# STB_DUTcarrier.net
KiCad netlist of a schematic drawn in Altium Designer
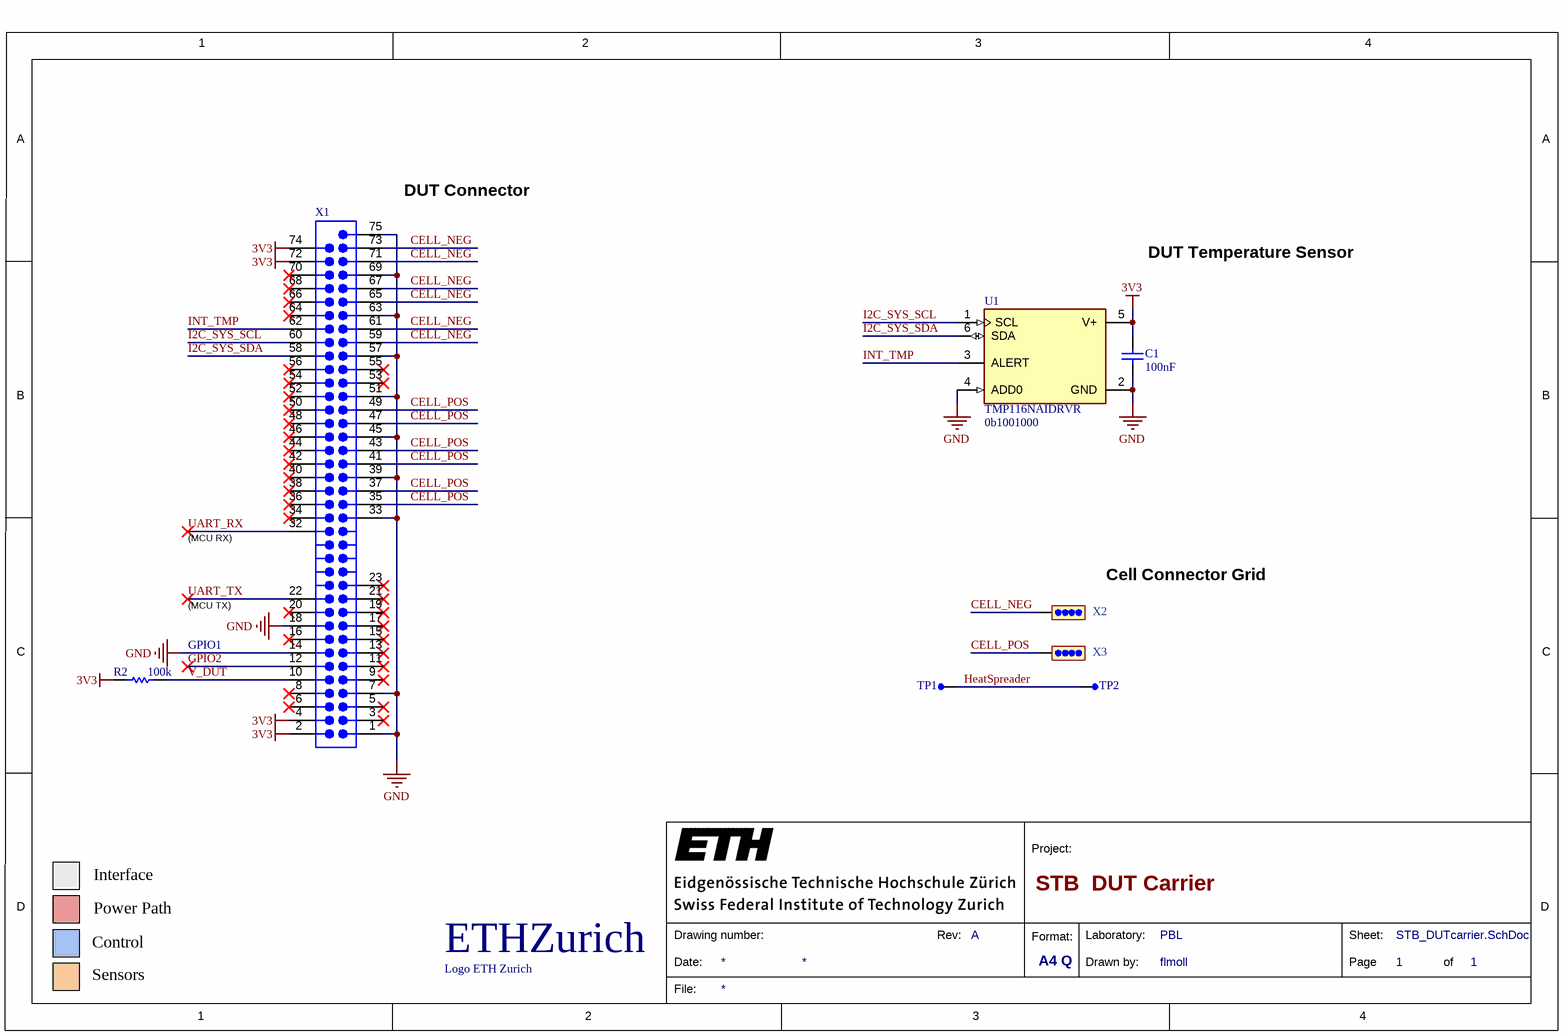
[diagram p0: STB_DUTcarrier.SchDoc]

(export (version "E")
  (design (tool "Eeschema 10.0.6"))
  (components
    (comp (ref "A1")
      (value "Logo ETH Zurich")
      (footprint "eth-zurich_5mm")
      (libsource (lib "ETHZ Vault") (part "Logo ETH Zurich"))
    )
    (comp (ref "C1")
      (value "100nF")
      (footprint "CAPC1050X55X23LL05T13")
      (description "Chip Capacitor, 100 nF, +/- 10%, 16 V, -55 to 125 degC, 0402 (1005 Metric), RoHS, Tape and Reel")
      (fields
        (field (name "MANUFACTURER") "Samsung Electro-Mechanics")
        (field (name "MANUFACTURER PART NUMBER") "CL05B104KO5NNNC")
      )
      (libsource (lib "Altium Content Vault") (part "CAP-NP-2"))
    )
    (comp (ref "R2")
      (value "100k")
      (footprint "RESC1005X40X25LL05T10")
      (fields
        (field (name "PART NUMBER") "RC0402FR-07100KL")
        (field (name "MANUFACTURER") "Yageo / Phycomp")
        (field (name "TOLERANCE") "1%")
      )
      (libsource (lib "Altium Content Vault") (part "RES"))
    )
    (comp (ref "TP1")
      (value "testPoint_1mm")
      (footprint "TP-SM-C-100")
      (description "testPoint 1mm")
      (libsource (lib "STB_Schlib") (part "testPoint_1mm"))
    )
    (comp (ref "TP2")
      (value "testPoint_1mm")
      (footprint "TP-SM-C-100")
      (description "testPoint 1mm")
      (libsource (lib "STB_Schlib") (part "testPoint_1mm"))
    )
    (comp (ref "U1")
      (value "TMP116NAIDRVR")
      (footprint "FP-DRV0006B-MFG")
      (description "SENSOR DIGITAL -55C-125C 6WSON")
      (fields
        (field (name "MANUFACTURER") "Texas Instruments")
        (field (name "OCTOPART") "https://octopart.com/tmp116naidrvr-texas+instruments-82367758")
        (field (name "ADDRESS") "0b1001000")
      )
      (libsource (lib "Altium Content Vault") (part "662a3f5fc0b2df02352a1f1bb70b9b8"))
    )
    (comp (ref "X1")
      (value "CONN PWR CARD EDGE PCB SLOT MALE")
      (footprint "CON-67_0.5MM_PCB_SLOT")
      (description "Mates with 2199119-4 - No BOM")
      (libsource (lib "ETHZ Vault") (part "CON-67_0.5mm_PCB_SLOT"))
    )
    (comp (ref "X2")
      (value "CellConnector")
      (footprint "cellConnector")
      (description "SMD dummy for cell connection")
      (libsource (lib "STB_Schlib") (part "CellConnector"))
    )
    (comp (ref "X3")
      (value "CellConnector")
      (footprint "cellConnector")
      (description "SMD dummy for cell connection")
      (libsource (lib "STB_Schlib") (part "CellConnector"))
    )
  )
  (nets
    (net (code "1") (name "/CELL_NEG") (class "Default")
      (node (ref "X1") (pin "59") (pinfunction "59_59") (pintype "passive"))
      (node (ref "X1") (pin "61") (pinfunction "61_61") (pintype "passive"))
      (node (ref "X1") (pin "65") (pinfunction "65_65") (pintype "passive"))
      (node (ref "X1") (pin "67") (pinfunction "67_67") (pintype "passive"))
      (node (ref "X1") (pin "71") (pinfunction "71_71") (pintype "passive"))
      (node (ref "X1") (pin "73") (pinfunction "73_73") (pintype "passive"))
      (node (ref "X2") (pin "1") (pinfunction "1_1") (pintype "passive"))
    )
    (net (code "2") (name "/CELL_POS") (class "Default")
      (node (ref "X1") (pin "35") (pinfunction "35_35") (pintype "passive"))
      (node (ref "X1") (pin "37") (pinfunction "37_37") (pintype "passive"))
      (node (ref "X1") (pin "41") (pinfunction "41_41") (pintype "passive"))
      (node (ref "X1") (pin "43") (pinfunction "43_43") (pintype "passive"))
      (node (ref "X1") (pin "47") (pinfunction "47_47") (pintype "passive"))
      (node (ref "X1") (pin "49") (pinfunction "49_49") (pintype "passive"))
      (node (ref "X3") (pin "1") (pinfunction "1_1") (pintype "passive"))
    )
    (net (code "3") (name "/GPIO2") (class "Default")
      (node (ref "X1") (pin "12") (pinfunction "12_12") (pintype "passive+no_connect"))
    )
    (net (code "4") (name "/HeatSpreader") (class "Default")
      (node (ref "TP1") (pin "1") (pinfunction "TP_1") (pintype "passive"))
      (node (ref "TP2") (pin "1") (pinfunction "TP_1") (pintype "passive"))
    )
    (net (code "5") (name "/I2C_SYS_SCL") (class "Default")
      (node (ref "U1") (pin "1") (pinfunction "SCL_1") (pintype "input"))
      (node (ref "X1") (pin "60") (pinfunction "55_60") (pintype "passive"))
    )
    (net (code "6") (name "/I2C_SYS_SDA") (class "Default")
      (node (ref "U1") (pin "6") (pinfunction "SDA_6") (pintype "bidirectional"))
      (node (ref "X1") (pin "58") (pinfunction "54_58") (pintype "passive"))
    )
    (net (code "7") (name "/INT_TMP") (class "Default")
      (node (ref "U1") (pin "3") (pinfunction "ALERT_3") (pintype "open_collector"))
      (node (ref "X1") (pin "62") (pinfunction "62_62") (pintype "passive"))
    )
    (net (code "8") (name "/UART_RX") (class "Default")
      (node (ref "X1") (pin "32") (pinfunction "32_32") (pintype "passive+no_connect"))
    )
    (net (code "9") (name "/UART_TX") (class "Default")
      (node (ref "X1") (pin "22") (pinfunction "22_22") (pintype "passive+no_connect"))
    )
    (net (code "10") (name "/V_DUT") (class "Default")
      (node (ref "R2") (pin "1") (pinfunction "1_1") (pintype "passive"))
      (node (ref "X1") (pin "10") (pinfunction "10_10") (pintype "passive"))
    )
    (net (code "11") (name "3V3") (class "Default")
      (node (ref "C1") (pin "2") (pinfunction "2_2") (pintype "passive"))
      (node (ref "R2") (pin "2") (pinfunction "2_2") (pintype "passive"))
      (node (ref "U1") (pin "5") (pinfunction "V+_5") (pintype "power_in"))
      (node (ref "X1") (pin "2") (pinfunction "2_2") (pintype "passive"))
      (node (ref "X1") (pin "4") (pinfunction "4_4") (pintype "passive"))
      (node (ref "X1") (pin "72") (pinfunction "72_72") (pintype "passive"))
      (node (ref "X1") (pin "74") (pinfunction "74_74") (pintype "passive"))
    )
    (net (code "12") (name "GND") (class "Default")
      (node (ref "C1") (pin "1") (pinfunction "1_1") (pintype "passive"))
      (node (ref "U1") (pin "2") (pinfunction "GND_2") (pintype "power_in"))
      (node (ref "U1") (pin "4") (pinfunction "ADD0_4") (pintype "input"))
      (node (ref "X1") (pin "1") (pinfunction "1_1") (pintype "passive"))
      (node (ref "X1") (pin "14") (pinfunction "14_14") (pintype "passive"))
      (node (ref "X1") (pin "18") (pinfunction "18_18") (pintype "passive"))
      (node (ref "X1") (pin "33") (pinfunction "33_33") (pintype "passive"))
      (node (ref "X1") (pin "39") (pinfunction "39_39") (pintype "passive"))
      (node (ref "X1") (pin "45") (pinfunction "45_45") (pintype "passive"))
      (node (ref "X1") (pin "51") (pinfunction "51_51") (pintype "passive"))
      (node (ref "X1") (pin "57") (pinfunction "57_57") (pintype "passive"))
      (node (ref "X1") (pin "63") (pinfunction "63_63") (pintype "passive"))
      (node (ref "X1") (pin "69") (pinfunction "69_69") (pintype "passive"))
      (node (ref "X1") (pin "7") (pinfunction "7_7") (pintype "passive"))
      (node (ref "X1") (pin "75") (pinfunction "75_75") (pintype "passive"))
    )
    (net (code "13") (name "unconnected-(X1-51-Pad52)") (class "Default")
      (node (ref "X1") (pin "52") (pinfunction "51_52") (pintype "passive+no_connect"))
    )
    (net (code "14") (name "unconnected-(X1-52-Pad54)") (class "Default")
      (node (ref "X1") (pin "54") (pinfunction "52_54") (pintype "passive+no_connect"))
    )
    (net (code "15") (name "unconnected-(X1-53-Pad56)") (class "Default")
      (node (ref "X1") (pin "56") (pinfunction "53_56") (pintype "passive+no_connect"))
    )
    (net (code "16") (name "unconnected-(X1-Pad3)") (class "Default")
      (node (ref "X1") (pin "3") (pinfunction "3_3") (pintype "passive+no_connect"))
    )
    (net (code "17") (name "unconnected-(X1-Pad5)") (class "Default")
      (node (ref "X1") (pin "5") (pinfunction "5_5") (pintype "passive+no_connect"))
    )
    (net (code "18") (name "unconnected-(X1-Pad6)") (class "Default")
      (node (ref "X1") (pin "6") (pinfunction "6_6") (pintype "passive+no_connect"))
    )
    (net (code "19") (name "unconnected-(X1-Pad8)") (class "Default")
      (node (ref "X1") (pin "8") (pinfunction "8_8") (pintype "passive+no_connect"))
    )
    (net (code "20") (name "unconnected-(X1-Pad9)") (class "Default")
      (node (ref "X1") (pin "9") (pinfunction "9_9") (pintype "passive+no_connect"))
    )
    (net (code "21") (name "unconnected-(X1-Pad11)") (class "Default")
      (node (ref "X1") (pin "11") (pinfunction "11_11") (pintype "passive+no_connect"))
    )
    (net (code "22") (name "unconnected-(X1-Pad13)") (class "Default")
      (node (ref "X1") (pin "13") (pinfunction "13_13") (pintype "passive+no_connect"))
    )
    (net (code "23") (name "unconnected-(X1-Pad15)") (class "Default")
      (node (ref "X1") (pin "15") (pinfunction "15_15") (pintype "passive+no_connect"))
    )
    (net (code "24") (name "unconnected-(X1-Pad16)") (class "Default")
      (node (ref "X1") (pin "16") (pinfunction "16_16") (pintype "passive+no_connect"))
    )
    (net (code "25") (name "unconnected-(X1-Pad17)") (class "Default")
      (node (ref "X1") (pin "17") (pinfunction "17_17") (pintype "passive+no_connect"))
    )
    (net (code "26") (name "unconnected-(X1-Pad19)") (class "Default")
      (node (ref "X1") (pin "19") (pinfunction "19_19") (pintype "passive+no_connect"))
    )
    (net (code "27") (name "unconnected-(X1-Pad20)") (class "Default")
      (node (ref "X1") (pin "20") (pinfunction "20_20") (pintype "passive+no_connect"))
    )
    (net (code "28") (name "unconnected-(X1-Pad21)") (class "Default")
      (node (ref "X1") (pin "21") (pinfunction "21_21") (pintype "passive+no_connect"))
    )
    (net (code "29") (name "unconnected-(X1-Pad23)") (class "Default")
      (node (ref "X1") (pin "23") (pinfunction "23_23") (pintype "passive+no_connect"))
    )
    (net (code "30") (name "unconnected-(X1-Pad34)") (class "Default")
      (node (ref "X1") (pin "34") (pinfunction "34_34") (pintype "passive+no_connect"))
    )
    (net (code "31") (name "unconnected-(X1-Pad36)") (class "Default")
      (node (ref "X1") (pin "36") (pinfunction "36_36") (pintype "passive+no_connect"))
    )
    (net (code "32") (name "unconnected-(X1-Pad38)") (class "Default")
      (node (ref "X1") (pin "38") (pinfunction "38_38") (pintype "passive+no_connect"))
    )
    (net (code "33") (name "unconnected-(X1-Pad40)") (class "Default")
      (node (ref "X1") (pin "40") (pinfunction "40_40") (pintype "passive+no_connect"))
    )
    (net (code "34") (name "unconnected-(X1-Pad42)") (class "Default")
      (node (ref "X1") (pin "42") (pinfunction "42_42") (pintype "passive+no_connect"))
    )
    (net (code "35") (name "unconnected-(X1-Pad44)") (class "Default")
      (node (ref "X1") (pin "44") (pinfunction "44_44") (pintype "passive+no_connect"))
    )
    (net (code "36") (name "unconnected-(X1-Pad46)") (class "Default")
      (node (ref "X1") (pin "46") (pinfunction "46_46") (pintype "passive+no_connect"))
    )
    (net (code "37") (name "unconnected-(X1-Pad48)") (class "Default")
      (node (ref "X1") (pin "48") (pinfunction "48_48") (pintype "passive+no_connect"))
    )
    (net (code "38") (name "unconnected-(X1-Pad50)") (class "Default")
      (node (ref "X1") (pin "50") (pinfunction "50_50") (pintype "passive+no_connect"))
    )
    (net (code "39") (name "unconnected-(X1-Pad53)") (class "Default")
      (node (ref "X1") (pin "53") (pinfunction "53_53") (pintype "passive+no_connect"))
    )
    (net (code "40") (name "unconnected-(X1-Pad55)") (class "Default")
      (node (ref "X1") (pin "55") (pinfunction "55_55") (pintype "passive+no_connect"))
    )
    (net (code "41") (name "unconnected-(X1-Pad64)") (class "Default")
      (node (ref "X1") (pin "64") (pinfunction "64_64") (pintype "passive+no_connect"))
    )
    (net (code "42") (name "unconnected-(X1-Pad66)") (class "Default")
      (node (ref "X1") (pin "66") (pinfunction "66_66") (pintype "passive+no_connect"))
    )
    (net (code "43") (name "unconnected-(X1-Pad68)") (class "Default")
      (node (ref "X1") (pin "68") (pinfunction "68_68") (pintype "passive+no_connect"))
    )
    (net (code "44") (name "unconnected-(X1-Pad70)") (class "Default")
      (node (ref "X1") (pin "70") (pinfunction "70_70") (pintype "passive+no_connect"))
    )
  )
)
